# SH04_-_OMAP-L137_SERIAL.net
KiCad netlist of a schematic drawn in Altium Designer
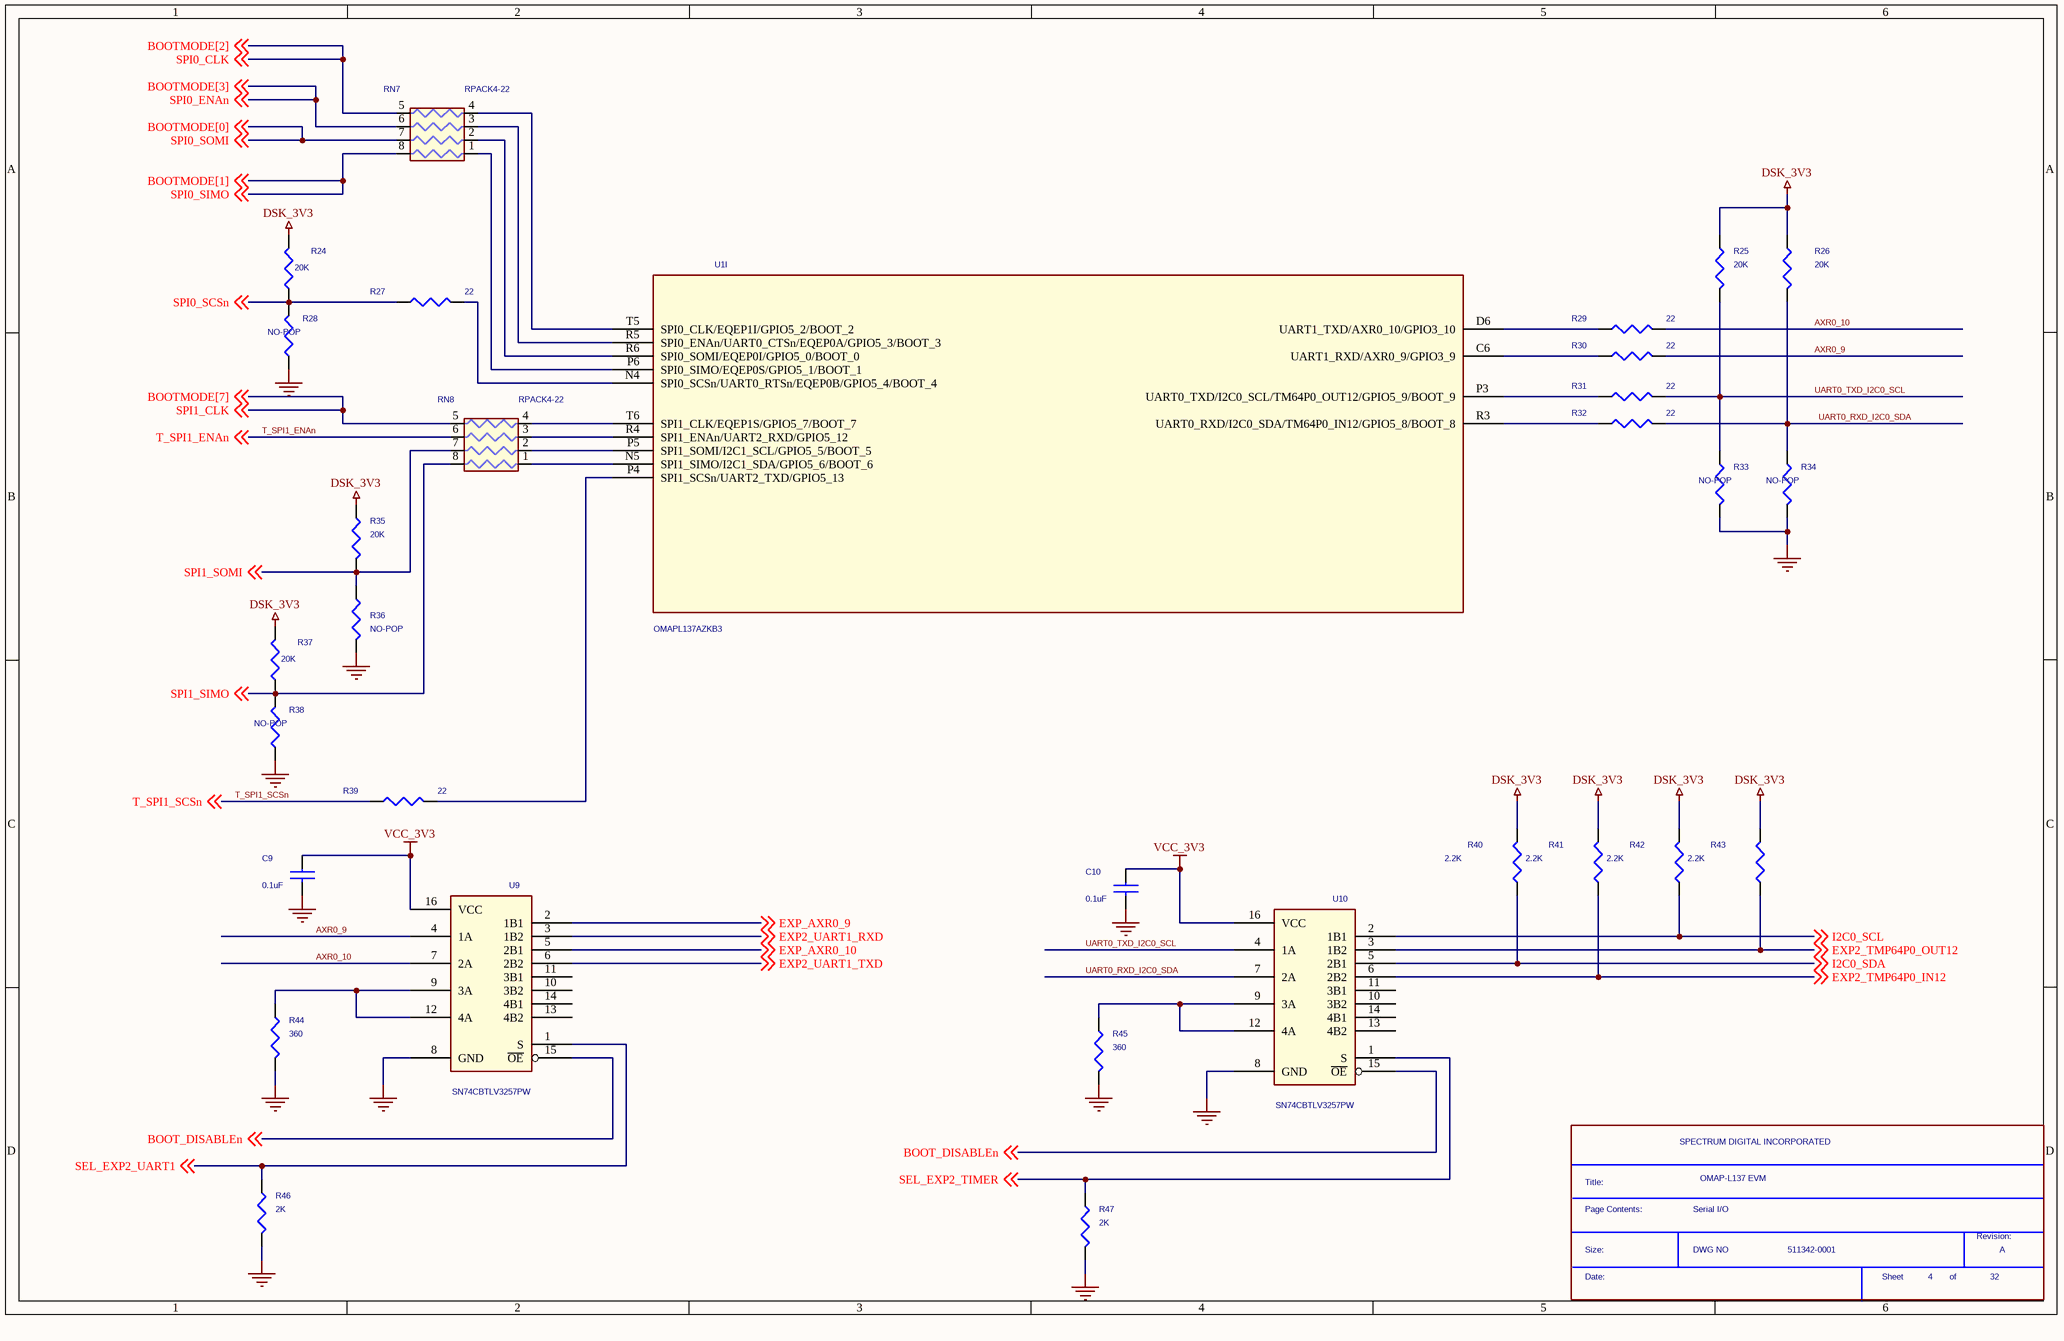
[diagram p0: SH04 - OMAP-L137 SERIAL.SchDoc]

(export (version "E")
  (design (tool "Eeschema 10.0.6"))
  (components
    (comp (ref "C9")
      (value "0.1uF")
      (footprint "c402-25")
      (fields (field (name "PART #") "101587-1100R"))
      (libsource (lib "*") (part "CAP NP"))
    )
    (comp (ref "C10")
      (value "0.1uF")
      (footprint "c402-25")
      (fields (field (name "PART #") "101587-1100R"))
      (libsource (lib "*") (part "CAP NP"))
    )
    (comp (ref "R24")
      (value "20K")
      (footprint "r402-25")
      (fields (field (name "PART #") "101370-2003R"))
      (libsource (lib "*") (part "R_1"))
    )
    (comp (ref "R25")
      (value "20K")
      (footprint "r402-25")
      (fields (field (name "PART #") "101370-2003R"))
      (libsource (lib "*") (part "R_1"))
    )
    (comp (ref "R26")
      (value "20K")
      (footprint "r402-25")
      (fields (field (name "PART #") "101370-2003R"))
      (libsource (lib "*") (part "R_1"))
    )
    (comp (ref "R27")
      (value "22")
      (footprint "r402-25")
      (fields (field (name "PART #") "101370-2200R"))
      (libsource (lib "*") (part "R_1"))
    )
    (comp (ref "R28")
      (value "NO-POP")
      (footprint "r402-25")
      (fields (field (name "PART #") "R0402-NOPOP"))
      (libsource (lib "*") (part "R_1"))
    )
    (comp (ref "R29")
      (value "22")
      (footprint "r402-25")
      (fields (field (name "PART #") "101370-2200R"))
      (libsource (lib "*") (part "R_1"))
    )
    (comp (ref "R30")
      (value "22")
      (footprint "r402-25")
      (fields (field (name "PART #") "101370-2200R"))
      (libsource (lib "*") (part "R_1"))
    )
    (comp (ref "R31")
      (value "22")
      (footprint "r402-25")
      (fields (field (name "PART #") "101370-2200R"))
      (libsource (lib "*") (part "R_1"))
    )
    (comp (ref "R32")
      (value "22")
      (footprint "r402-25")
      (fields (field (name "PART #") "101370-2200R"))
      (libsource (lib "*") (part "R_1"))
    )
    (comp (ref "R33")
      (value "NO-POP")
      (footprint "r402-25")
      (fields (field (name "PART #") "R0402-NOPOP"))
      (libsource (lib "*") (part "R_1"))
    )
    (comp (ref "R34")
      (value "NO-POP")
      (footprint "r402-25")
      (fields (field (name "PART #") "R0402-NOPOP"))
      (libsource (lib "*") (part "R_1"))
    )
    (comp (ref "R35")
      (value "20K")
      (footprint "r402-25")
      (fields (field (name "PART #") "101370-2003R"))
      (libsource (lib "*") (part "R_1"))
    )
    (comp (ref "R36")
      (value "NO-POP")
      (footprint "r402-25")
      (fields (field (name "PART #") "R0402-NOPOP"))
      (libsource (lib "*") (part "R_1"))
    )
    (comp (ref "R37")
      (value "20K")
      (footprint "r402-25")
      (fields (field (name "PART #") "101370-2003R"))
      (libsource (lib "*") (part "R_1"))
    )
    (comp (ref "R38")
      (value "NO-POP")
      (footprint "r402-25")
      (fields (field (name "PART #") "R0402-NOPOP"))
      (libsource (lib "*") (part "R_1"))
    )
    (comp (ref "R39")
      (value "22")
      (footprint "r402-25")
      (fields (field (name "PART #") "101370-2200R"))
      (libsource (lib "*") (part "R_1"))
    )
    (comp (ref "R40")
      (value "2.2K")
      (footprint "r402-25")
      (fields (field (name "PART #") "101370-2202R"))
      (libsource (lib "*") (part "R"))
    )
    (comp (ref "R41")
      (value "2.2K")
      (footprint "r402-25")
      (fields (field (name "PART #") "101370-2202R"))
      (libsource (lib "*") (part "R"))
    )
    (comp (ref "R42")
      (value "2.2K")
      (footprint "r402-25")
      (fields (field (name "PART #") "101370-2202R"))
      (libsource (lib "*") (part "R"))
    )
    (comp (ref "R43")
      (value "2.2K")
      (footprint "r402-25")
      (fields (field (name "PART #") "101370-2202R"))
      (libsource (lib "*") (part "R"))
    )
    (comp (ref "R44")
      (value "360")
      (footprint "r402-25")
      (fields (field (name "PART #") "101370-3601R"))
      (libsource (lib "*") (part "R"))
    )
    (comp (ref "R45")
      (value "360")
      (footprint "r402-25")
      (fields (field (name "PART #") "101370-3601R"))
      (libsource (lib "*") (part "R"))
    )
    (comp (ref "R46")
      (value "2K")
      (footprint "r402-25")
      (fields (field (name "PART #") "101370-2002R"))
      (libsource (lib "*") (part "R"))
    )
    (comp (ref "R47")
      (value "2K")
      (footprint "r402-25")
      (fields (field (name "PART #") "101370-2002R"))
      (libsource (lib "*") (part "R"))
    )
    (comp (ref "RN7")
      (value "RPACK4-22")
      (footprint "rpak8-10x25-28v")
      (fields (field (name "PART #") "101327-2200R"))
      (libsource (lib "*") (part "R-Pak4_0"))
    )
    (comp (ref "RN8")
      (value "RPACK4-22")
      (footprint "rpak8-10x25-28v")
      (fields (field (name "PART #") "101327-2200R"))
      (libsource (lib "*") (part "R-Pak4_0"))
    )
    (comp (ref "U1")
      (value "OMAPL137AZKB3")
      (footprint "skt256-6064")
      (fields (field (name "PART #") "102772-0001"))
      (libsource (lib "*") (part "PRIMUS_BGA_1"))
    )
    (comp (ref "U9")
      (value "SN74CBTLV3257PW")
      (footprint "TSSOP-16")
      (description "IC, Quad 2-1 Multiplexer")
      (fields (field (name "MFG") "TI") (field (name "PART #") "101670-0001R"))
      (libsource (lib "*") (part "SN74CBT3257PW"))
    )
    (comp (ref "U10")
      (value "SN74CBTLV3257PW")
      (footprint "TSSOP-16")
      (description "IC, Quad 2-1 Multiplexer")
      (fields (field (name "MFG") "TI") (field (name "PART #") "101670-0001R"))
      (libsource (lib "*") (part "SN74CBT3257PW"))
    )
  )
  (nets
    (net (code "1") (name "/AXR0_9") (class "Default")
      (node (ref "R30") (pin "2") (pinfunction "2_2") (pintype "passive"))
      (node (ref "U9") (pin "4") (pinfunction "1A_4") (pintype "passive"))
    )
    (net (code "2") (name "/AXR0_10") (class "Default")
      (node (ref "R29") (pin "2") (pinfunction "2_2") (pintype "passive"))
      (node (ref "U9") (pin "7") (pinfunction "2A_7") (pintype "passive"))
    )
    (net (code "3") (name "/UART0_RXD_I2C0_SDA") (class "Default")
      (node (ref "R26") (pin "2") (pinfunction "2_2") (pintype "passive"))
      (node (ref "R32") (pin "2") (pinfunction "2_2") (pintype "passive"))
      (node (ref "R34") (pin "2") (pinfunction "2_2") (pintype "passive"))
      (node (ref "U10") (pin "7") (pinfunction "2A_7") (pintype "passive"))
    )
    (net (code "4") (name "/UART0_TXD_I2C0_SCL") (class "Default")
      (node (ref "R25") (pin "2") (pinfunction "2_2") (pintype "passive"))
      (node (ref "R31") (pin "2") (pinfunction "2_2") (pintype "passive"))
      (node (ref "R33") (pin "2") (pinfunction "2_2") (pintype "passive"))
      (node (ref "U10") (pin "4") (pinfunction "1A_4") (pintype "passive"))
    )
    (net (code "5") (name "BOOTMODE[0]") (class "Default")
      (node (ref "RN7") (pin "7") (pinfunction "R2B_7") (pintype "passive"))
    )
    (net (code "6") (name "BOOTMODE[1]") (class "Default")
      (node (ref "RN7") (pin "8") (pinfunction "R1B_8") (pintype "passive"))
    )
    (net (code "7") (name "BOOTMODE[2]") (class "Default")
      (node (ref "RN7") (pin "5") (pinfunction "R4B_5") (pintype "passive"))
    )
    (net (code "8") (name "BOOTMODE[3]") (class "Default")
      (node (ref "RN7") (pin "6") (pinfunction "R3B_6") (pintype "passive"))
    )
    (net (code "9") (name "BOOTMODE[7]") (class "Default")
      (node (ref "RN8") (pin "5") (pinfunction "R4B_5") (pintype "passive"))
    )
    (net (code "10") (name "BOOT_DISABLEn") (class "Default")
      (node (ref "U10") (pin "15") (pinfunction "~{OE}_15") (pintype "passive"))
      (node (ref "U9") (pin "15") (pinfunction "~{OE}_15") (pintype "passive"))
    )
    (net (code "11") (name "DSK_3V3") (class "Default")
      (node (ref "R24") (pin "1") (pinfunction "1_1") (pintype "passive"))
      (node (ref "R25") (pin "1") (pinfunction "1_1") (pintype "passive"))
      (node (ref "R26") (pin "1") (pinfunction "1_1") (pintype "passive"))
      (node (ref "R35") (pin "1") (pinfunction "1_1") (pintype "passive"))
      (node (ref "R37") (pin "1") (pinfunction "1_1") (pintype "passive"))
      (node (ref "R40") (pin "1") (pinfunction "1_1") (pintype "passive"))
      (node (ref "R41") (pin "1") (pinfunction "1_1") (pintype "passive"))
      (node (ref "R42") (pin "1") (pinfunction "1_1") (pintype "passive"))
      (node (ref "R43") (pin "1") (pinfunction "1_1") (pintype "passive"))
    )
    (net (code "12") (name "EXP2_TMP64P0_IN12") (class "Default")
      (node (ref "R41") (pin "2") (pinfunction "2_2") (pintype "passive"))
      (node (ref "U10") (pin "6") (pinfunction "2B2_6") (pintype "passive"))
    )
    (net (code "13") (name "EXP2_TMP64P0_OUT12") (class "Default")
      (node (ref "R43") (pin "2") (pinfunction "2_2") (pintype "passive"))
      (node (ref "U10") (pin "3") (pinfunction "1B2_3") (pintype "passive"))
    )
    (net (code "14") (name "EXP2_UART1_RXD") (class "Default")
      (node (ref "U9") (pin "3") (pinfunction "1B2_3") (pintype "passive"))
    )
    (net (code "15") (name "EXP2_UART1_TXD") (class "Default")
      (node (ref "U9") (pin "6") (pinfunction "2B2_6") (pintype "passive"))
    )
    (net (code "16") (name "EXP_AXR0_9") (class "Default")
      (node (ref "U9") (pin "2") (pinfunction "1B1_2") (pintype "passive"))
    )
    (net (code "17") (name "EXP_AXR0_10") (class "Default")
      (node (ref "U9") (pin "5") (pinfunction "2B1_5") (pintype "passive"))
    )
    (net (code "18") (name "GND") (class "Default")
      (node (ref "C10") (pin "2") (pinfunction "2_2") (pintype "passive"))
      (node (ref "C9") (pin "2") (pinfunction "2_2") (pintype "passive"))
      (node (ref "R28") (pin "2") (pinfunction "2_2") (pintype "passive"))
      (node (ref "R33") (pin "1") (pinfunction "1_1") (pintype "passive"))
      (node (ref "R34") (pin "1") (pinfunction "1_1") (pintype "passive"))
      (node (ref "R36") (pin "2") (pinfunction "2_2") (pintype "passive"))
      (node (ref "R38") (pin "2") (pinfunction "2_2") (pintype "passive"))
      (node (ref "R44") (pin "2") (pinfunction "2_2") (pintype "passive"))
      (node (ref "R45") (pin "2") (pinfunction "2_2") (pintype "passive"))
      (node (ref "R46") (pin "2") (pinfunction "2_2") (pintype "passive"))
      (node (ref "R47") (pin "2") (pinfunction "2_2") (pintype "passive"))
      (node (ref "U10") (pin "8") (pinfunction "GND_8") (pintype "passive"))
      (node (ref "U9") (pin "8") (pinfunction "GND_8") (pintype "passive"))
    )
    (net (code "19") (name "I2C0_SCL") (class "Default")
      (node (ref "R42") (pin "2") (pinfunction "2_2") (pintype "passive"))
      (node (ref "U10") (pin "2") (pinfunction "1B1_2") (pintype "passive"))
    )
    (net (code "20") (name "I2C0_SDA") (class "Default")
      (node (ref "R40") (pin "2") (pinfunction "2_2") (pintype "passive"))
      (node (ref "U10") (pin "5") (pinfunction "2B1_5") (pintype "passive"))
    )
    (net (code "21") (name "Net-(RN7-R1A)") (class "Default")
      (node (ref "RN7") (pin "1") (pinfunction "R1A_1") (pintype "passive"))
      (node (ref "U1") (pin "P6") (pinfunction "SPI0_SIMO/EQEP0S/GPIO5_1/BOOT_1_P6") (pintype "passive"))
    )
    (net (code "22") (name "Net-(RN7-R2A)") (class "Default")
      (node (ref "RN7") (pin "2") (pinfunction "R2A_2") (pintype "passive"))
      (node (ref "U1") (pin "R6") (pinfunction "SPI0_SOMI/EQEP0I/GPIO5_0/BOOT_0_R6") (pintype "passive"))
    )
    (net (code "23") (name "Net-(RN7-R3A)") (class "Default")
      (node (ref "RN7") (pin "3") (pinfunction "R3A_3") (pintype "passive"))
      (node (ref "U1") (pin "R5") (pinfunction "SPI0_ENAn/UART0_CTSn/EQEP0A/GPIO5_3/BOOT_3_R5") (pintype "passive"))
    )
    (net (code "24") (name "Net-(RN7-R4A)") (class "Default")
      (node (ref "RN7") (pin "4") (pinfunction "R4A_4") (pintype "passive"))
      (node (ref "U1") (pin "T5") (pinfunction "SPI0_CLK/EQEP1I/GPIO5_2/BOOT_2_T5") (pintype "passive"))
    )
    (net (code "25") (name "Net-(RN8-R1A)") (class "Default")
      (node (ref "RN8") (pin "1") (pinfunction "R1A_1") (pintype "passive"))
      (node (ref "U1") (pin "N5") (pinfunction "SPI1_SIMO/I2C1_SDA/GPIO5_6/BOOT_6_N5") (pintype "passive"))
    )
    (net (code "26") (name "Net-(RN8-R2A)") (class "Default")
      (node (ref "RN8") (pin "2") (pinfunction "R2A_2") (pintype "passive"))
      (node (ref "U1") (pin "P5") (pinfunction "SPI1_SOMI/I2C1_SCL/GPIO5_5/BOOT_5_P5") (pintype "passive"))
    )
    (net (code "27") (name "Net-(RN8-R3A)") (class "Default")
      (node (ref "RN8") (pin "3") (pinfunction "R3A_3") (pintype "passive"))
      (node (ref "U1") (pin "R4") (pinfunction "SPI1_ENAn/UART2_RXD/GPIO5_12_R4") (pintype "passive"))
    )
    (net (code "28") (name "Net-(RN8-R4A)") (class "Default")
      (node (ref "RN8") (pin "4") (pinfunction "R4A_4") (pintype "passive"))
      (node (ref "U1") (pin "T6") (pinfunction "SPI1_CLK/EQEP1S/GPIO5_7/BOOT_7_T6") (pintype "passive"))
    )
    (net (code "29") (name "Net-(U1I-SPI0_SCSn{slash}UART0_RTSn{slash}EQEP0B{slash}GPIO5_4{slash}BOOT_4)") (class "Default")
      (node (ref "R27") (pin "2") (pinfunction "2_2") (pintype "passive"))
      (node (ref "U1") (pin "N4") (pinfunction "SPI0_SCSn/UART0_RTSn/EQEP0B/GPIO5_4/BOOT_4_N4") (pintype "passive"))
    )
    (net (code "30") (name "Net-(U1I-SPI1_SCSn{slash}UART2_TXD{slash}GPIO5_13)") (class "Default")
      (node (ref "R39") (pin "2") (pinfunction "2_2") (pintype "passive"))
      (node (ref "U1") (pin "P4") (pinfunction "SPI1_SCSn/UART2_TXD/GPIO5_13_P4") (pintype "passive"))
    )
    (net (code "31") (name "Net-(U1I-UART0_RXD{slash}I2C0_SDA{slash}TM64P0_IN12{slash}GPIO5_8{slash}BOOT_8)") (class "Default")
      (node (ref "R32") (pin "1") (pinfunction "1_1") (pintype "passive"))
      (node (ref "U1") (pin "R3") (pinfunction "UART0_RXD/I2C0_SDA/TM64P0_IN12/GPIO5_8/BOOT_8_R3") (pintype "passive"))
    )
    (net (code "32") (name "Net-(U1I-UART0_TXD{slash}I2C0_SCL{slash}TM64P0_OUT12{slash}GPIO5_9{slash}BOOT_9)") (class "Default")
      (node (ref "R31") (pin "1") (pinfunction "1_1") (pintype "passive"))
      (node (ref "U1") (pin "P3") (pinfunction "UART0_TXD/I2C0_SCL/TM64P0_OUT12/GPIO5_9/BOOT_9_P3") (pintype "passive"))
    )
    (net (code "33") (name "Net-(U1I-UART1_RXD{slash}AXR0_9{slash}GPIO3_9)") (class "Default")
      (node (ref "R30") (pin "1") (pinfunction "1_1") (pintype "passive"))
      (node (ref "U1") (pin "C6") (pinfunction "UART1_RXD/AXR0_9/GPIO3_9_C6") (pintype "passive"))
    )
    (net (code "34") (name "Net-(U1I-UART1_TXD{slash}AXR0_10{slash}GPIO3_10)") (class "Default")
      (node (ref "R29") (pin "1") (pinfunction "1_1") (pintype "passive"))
      (node (ref "U1") (pin "D6") (pinfunction "UART1_TXD/AXR0_10/GPIO3_10_D6") (pintype "passive"))
    )
    (net (code "35") (name "Net-(U9-3A)") (class "Default")
      (node (ref "R44") (pin "1") (pinfunction "1_1") (pintype "passive"))
      (node (ref "U9") (pin "12") (pinfunction "4A_12") (pintype "passive"))
      (node (ref "U9") (pin "9") (pinfunction "3A_9") (pintype "passive"))
    )
    (net (code "36") (name "Net-(U10-3A)") (class "Default")
      (node (ref "R45") (pin "1") (pinfunction "1_1") (pintype "passive"))
      (node (ref "U10") (pin "12") (pinfunction "4A_12") (pintype "passive"))
      (node (ref "U10") (pin "9") (pinfunction "3A_9") (pintype "passive"))
    )
    (net (code "37") (name "SEL_EXP2_TIMER") (class "Default")
      (node (ref "R47") (pin "1") (pinfunction "1_1") (pintype "passive"))
      (node (ref "U10") (pin "1") (pinfunction "S_1") (pintype "passive"))
    )
    (net (code "38") (name "SEL_EXP2_UART1") (class "Default")
      (node (ref "R46") (pin "1") (pinfunction "1_1") (pintype "passive"))
      (node (ref "U9") (pin "1") (pinfunction "S_1") (pintype "passive"))
    )
    (net (code "39") (name "SPI0_SCSn") (class "Default")
      (node (ref "R24") (pin "2") (pinfunction "2_2") (pintype "passive"))
      (node (ref "R27") (pin "1") (pinfunction "1_1") (pintype "passive"))
      (node (ref "R28") (pin "1") (pinfunction "1_1") (pintype "passive"))
    )
    (net (code "40") (name "SPI1_SIMO") (class "Default")
      (node (ref "R37") (pin "2") (pinfunction "2_2") (pintype "passive"))
      (node (ref "R38") (pin "1") (pinfunction "1_1") (pintype "passive"))
      (node (ref "RN8") (pin "8") (pinfunction "R1B_8") (pintype "passive"))
    )
    (net (code "41") (name "SPI1_SOMI") (class "Default")
      (node (ref "R35") (pin "2") (pinfunction "2_2") (pintype "passive"))
      (node (ref "R36") (pin "1") (pinfunction "1_1") (pintype "passive"))
      (node (ref "RN8") (pin "7") (pinfunction "R2B_7") (pintype "passive"))
    )
    (net (code "42") (name "T_SPI1_ENAn") (class "Default")
      (node (ref "RN8") (pin "6") (pinfunction "R3B_6") (pintype "passive"))
    )
    (net (code "43") (name "T_SPI1_SCSn") (class "Default")
      (node (ref "R39") (pin "1") (pinfunction "1_1") (pintype "passive"))
    )
    (net (code "44") (name "VCC_3V3") (class "Default")
      (node (ref "C10") (pin "1") (pinfunction "1_1") (pintype "passive"))
      (node (ref "C9") (pin "1") (pinfunction "1_1") (pintype "passive"))
      (node (ref "U10") (pin "16") (pinfunction "VCC_16") (pintype "passive"))
      (node (ref "U9") (pin "16") (pinfunction "VCC_16") (pintype "passive"))
    )
    (net (code "45") (name "unconnected-(U9-3B1-Pad11)") (class "Default")
      (node (ref "U9") (pin "11") (pinfunction "3B1_11") (pintype "passive"))
    )
    (net (code "46") (name "unconnected-(U9-3B2-Pad10)") (class "Default")
      (node (ref "U9") (pin "10") (pinfunction "3B2_10") (pintype "passive"))
    )
    (net (code "47") (name "unconnected-(U9-4B1-Pad14)") (class "Default")
      (node (ref "U9") (pin "14") (pinfunction "4B1_14") (pintype "passive"))
    )
    (net (code "48") (name "unconnected-(U9-4B2-Pad13)") (class "Default")
      (node (ref "U9") (pin "13") (pinfunction "4B2_13") (pintype "passive"))
    )
    (net (code "49") (name "unconnected-(U10-3B1-Pad11)") (class "Default")
      (node (ref "U10") (pin "11") (pinfunction "3B1_11") (pintype "passive"))
    )
    (net (code "50") (name "unconnected-(U10-3B2-Pad10)") (class "Default")
      (node (ref "U10") (pin "10") (pinfunction "3B2_10") (pintype "passive"))
    )
    (net (code "51") (name "unconnected-(U10-4B1-Pad14)") (class "Default")
      (node (ref "U10") (pin "14") (pinfunction "4B1_14") (pintype "passive"))
    )
    (net (code "52") (name "unconnected-(U10-4B2-Pad13)") (class "Default")
      (node (ref "U10") (pin "13") (pinfunction "4B2_13") (pintype "passive"))
    )
  )
)
